# K22F.net
KiCad netlist of a schematic drawn in Altium Designer
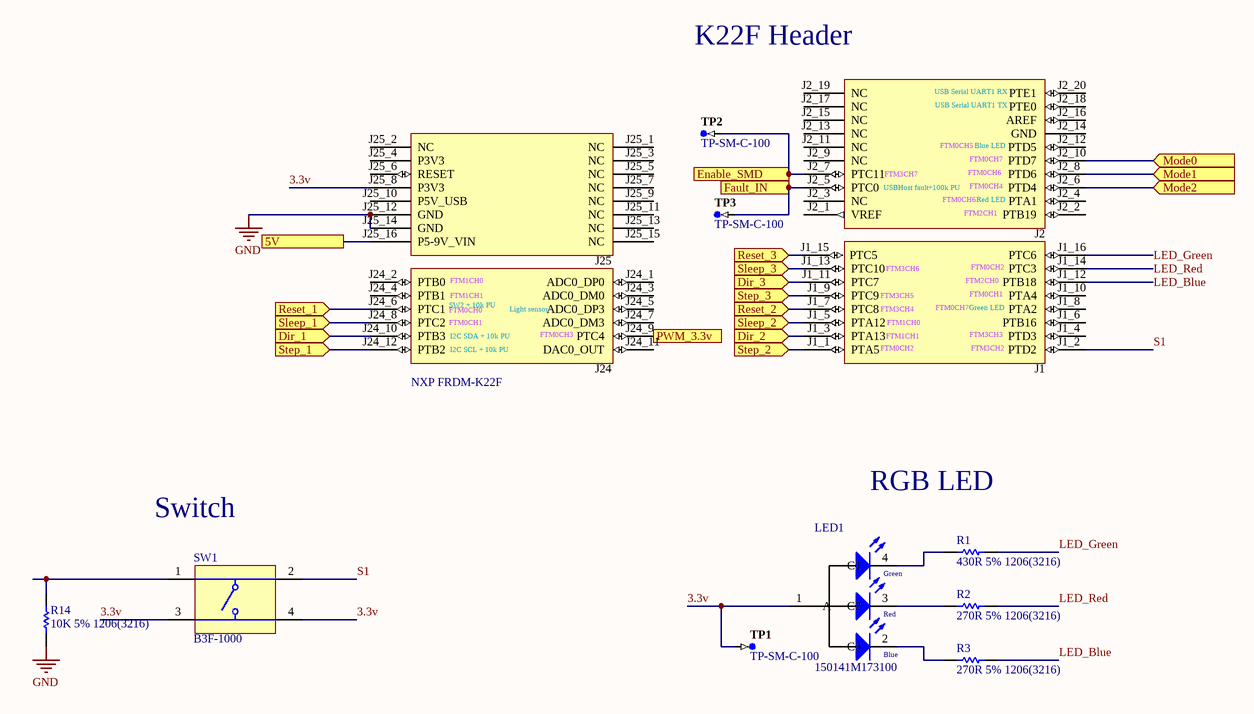
[diagram p0: K22F.SchDoc]

(export (version "E")
  (design (tool "Eeschema 10.0.6"))
  (components
    (comp (ref "*1")
      (value "NXP FRDM-K22F")
      (footprint "FRDM-K22F")
      (libsource (lib "JCULibrary_AS2 (1)") (part "NXP FRDM-K22F"))
    )
    (comp (ref "LED1")
      (value "150141M173100")
      (footprint "3528_A")
      (description "SMD Full-Color Top LED, WL-SFTW, Red & Green & Blue")
      (fields (field (name "MANUFACTURER") "Wuerth Elektronik"))
      (libsource (lib "Altium Content Vault") (part "WE-LED_RGB_A1B2R3G4-4"))
    )
    (comp (ref "R1")
      (value "430R 5% 1206(3216)")
      (footprint "RESC1206(3216)_L")
      (description "430R 0.25W 5% 1206 (3216 Metric)  SMD")
      (fields (field (name "POWER") "0.25 W") (field (name "TOLERANCE") "5 %"))
      (libsource (lib "Altium Content Vault") (part "RES"))
    )
    (comp (ref "R2")
      (value "270R 5% 1206(3216)")
      (footprint "RESC1206(3216)_N")
      (description "270R 0.25W 5% 1206 (3216 Metric)  SMD")
      (fields (field (name "TOLERANCE") "5 %") (field (name "POWER") "0.25 W"))
      (libsource (lib "Altium Content Vault") (part "RES"))
    )
    (comp (ref "R3")
      (value "270R 5% 1206(3216)")
      (footprint "RESC1206(3216)_N")
      (description "270R 0.25W 5% 1206 (3216 Metric)  SMD")
      (fields (field (name "TOLERANCE") "5 %") (field (name "POWER") "0.25 W"))
      (libsource (lib "Altium Content Vault") (part "RES"))
    )
    (comp (ref "R14")
      (value "10K 5% 1206(3216)")
      (footprint "RESC1206(3216)_M")
      (description "10K 0.25W 5% 1206 (3216 Metric)  SMD")
      (fields (field (name "POWER") "0.25 W") (field (name "TOLERANCE") "5 %"))
      (libsource (lib "Altium Content Vault") (part "RES"))
    )
    (comp (ref "SW1")
      (value "B3F-1000")
      (footprint "OMRON-B3F-1000-4_V")
      (description "Tactile Switch, SPST-NO, 0.05 A, 5 to 24 V, -25 to 70 degC, 4-Pin THD, RoHS, Bulk")
      (libsource (lib "Altium Content Vault") (part "SW-SPST-4_A"))
    )
    (comp (ref "TP1")
      (value "TP-SM-C-100")
      (footprint "TP-SM-C-100")
      (description "Test Point, Surface Mount, Circular, Pad Diameter 1 mm")
      (fields (field (name "MANUFACTURER") "No Vendor"))
      (libsource (lib "Altium Content Vault") (part "TP-SM"))
    )
    (comp (ref "TP2")
      (value "TP-SM-C-100")
      (footprint "TP-SM-C-100")
      (description "Test Point, Surface Mount, Circular, Pad Diameter 1 mm")
      (fields (field (name "MANUFACTURER") "No Vendor"))
      (libsource (lib "Altium Content Vault") (part "TP-SM"))
    )
    (comp (ref "TP3")
      (value "TP-SM-C-100")
      (footprint "TP-SM-C-100")
      (description "Test Point, Surface Mount, Circular, Pad Diameter 1 mm")
      (fields (field (name "MANUFACTURER") "No Vendor"))
      (libsource (lib "Altium Content Vault") (part "TP-SM"))
    )
  )
  (nets
    (net (code "1") (name "/3.3v") (class "Default")
      (node (ref "*1") (pin "J25_8") (pinfunction "P3V3_J25_8") (pintype "power_in"))
      (node (ref "LED1") (pin "1") (pinfunction "A_1") (pintype "passive"))
      (node (ref "SW1") (pin "3") (pinfunction "3_3") (pintype "passive"))
      (node (ref "SW1") (pin "4") (pinfunction "4_4") (pintype "passive"))
      (node (ref "TP1") (pin "1") (pinfunction "1_1") (pintype "input"))
    )
    (net (code "2") (name "/5V") (class "Default")
      (node (ref "*1") (pin "J25_16") (pinfunction "P5-9V_VIN_J25_16") (pintype "power_in"))
    )
    (net (code "3") (name "/Dir_1") (class "Default")
      (node (ref "*1") (pin "J24_10") (pinfunction "PTB3_J24_10") (pintype "bidirectional"))
    )
    (net (code "4") (name "/Dir_2") (class "Default")
      (node (ref "*1") (pin "J1_3") (pinfunction "PTA13_J1_3") (pintype "bidirectional"))
    )
    (net (code "5") (name "/Dir_3") (class "Default")
      (node (ref "*1") (pin "J1_11") (pinfunction "PTC7_J1_11") (pintype "bidirectional"))
    )
    (net (code "6") (name "/Enable_SMD") (class "Default")
      (node (ref "*1") (pin "J2_7") (pinfunction "PTC11_J2_7") (pintype "bidirectional"))
      (node (ref "TP2") (pin "1") (pinfunction "1_1") (pintype "input"))
    )
    (net (code "7") (name "/Fault_IN") (class "Default")
      (node (ref "*1") (pin "J2_5") (pinfunction "PTC0_J2_5") (pintype "bidirectional"))
      (node (ref "TP3") (pin "1") (pinfunction "1_1") (pintype "input"))
    )
    (net (code "8") (name "/LED_Blue") (class "Default")
      (node (ref "*1") (pin "J1_12") (pinfunction "PTB18_J1_12") (pintype "bidirectional"))
      (node (ref "R3") (pin "2") (pinfunction "2_2") (pintype "passive"))
    )
    (net (code "9") (name "/LED_Green") (class "Default")
      (node (ref "*1") (pin "J1_16") (pinfunction "PTC6_J1_16") (pintype "bidirectional"))
      (node (ref "R1") (pin "2") (pinfunction "2_2") (pintype "passive"))
    )
    (net (code "10") (name "/LED_Red") (class "Default")
      (node (ref "*1") (pin "J1_14") (pinfunction "PTC3_J1_14") (pintype "bidirectional"))
      (node (ref "R2") (pin "2") (pinfunction "2_2") (pintype "passive"))
    )
    (net (code "11") (name "/Mode0") (class "Default")
      (node (ref "*1") (pin "J2_10") (pinfunction "PTD7_J2_10") (pintype "bidirectional"))
    )
    (net (code "12") (name "/Mode1") (class "Default")
      (node (ref "*1") (pin "J2_8") (pinfunction "PTD6_J2_8") (pintype "bidirectional"))
    )
    (net (code "13") (name "/Mode2") (class "Default")
      (node (ref "*1") (pin "J2_6") (pinfunction "PTD4_J2_6") (pintype "bidirectional"))
    )
    (net (code "14") (name "/PWM_3.3v") (class "Default")
      (node (ref "*1") (pin "J24_9") (pinfunction "PTC4_J24_9") (pintype "bidirectional"))
    )
    (net (code "15") (name "/Reset_1") (class "Default")
      (node (ref "*1") (pin "J24_6") (pinfunction "PTC1_J24_6") (pintype "bidirectional"))
    )
    (net (code "16") (name "/Reset_2") (class "Default")
      (node (ref "*1") (pin "J1_7") (pinfunction "PTC8_J1_7") (pintype "bidirectional"))
    )
    (net (code "17") (name "/Reset_3") (class "Default")
      (node (ref "*1") (pin "J1_15") (pinfunction "PTC5_J1_15") (pintype "bidirectional"))
    )
    (net (code "18") (name "/S1") (class "Default")
      (node (ref "*1") (pin "J1_2") (pinfunction "PTD2_J1_2") (pintype "bidirectional"))
      (node (ref "SW1") (pin "2") (pinfunction "2_2") (pintype "passive"))
    )
    (net (code "19") (name "/Sleep_1") (class "Default")
      (node (ref "*1") (pin "J24_8") (pinfunction "PTC2_J24_8") (pintype "bidirectional"))
    )
    (net (code "20") (name "/Sleep_2") (class "Default")
      (node (ref "*1") (pin "J1_5") (pinfunction "PTA12_J1_5") (pintype "bidirectional"))
    )
    (net (code "21") (name "/Sleep_3") (class "Default")
      (node (ref "*1") (pin "J1_13") (pinfunction "PTC10_J1_13") (pintype "bidirectional"))
    )
    (net (code "22") (name "/Step_1") (class "Default")
      (node (ref "*1") (pin "J24_12") (pinfunction "PTB2_J24_12") (pintype "bidirectional"))
    )
    (net (code "23") (name "/Step_2") (class "Default")
      (node (ref "*1") (pin "J1_1") (pinfunction "PTA5_J1_1") (pintype "bidirectional"))
    )
    (net (code "24") (name "/Step_3") (class "Default")
      (node (ref "*1") (pin "J1_9") (pinfunction "PTC9_J1_9") (pintype "bidirectional"))
    )
    (net (code "25") (name "GND") (class "Default")
      (node (ref "*1") (pin "J25_12") (pinfunction "GND_J25_12") (pintype "power_in"))
      (node (ref "*1") (pin "J25_14") (pinfunction "GND_J25_14") (pintype "power_in"))
      (node (ref "R14") (pin "1") (pinfunction "1_1") (pintype "passive"))
    )
    (net (code "26") (name "Net-(LED1-C1)") (class "Default")
      (node (ref "LED1") (pin "4") (pinfunction "C1_4") (pintype "passive"))
      (node (ref "R1") (pin "1") (pinfunction "1_1") (pintype "passive"))
    )
    (net (code "27") (name "Net-(LED1-C2)") (class "Default")
      (node (ref "LED1") (pin "3") (pinfunction "C2_3") (pintype "passive"))
      (node (ref "R2") (pin "1") (pinfunction "1_1") (pintype "passive"))
    )
    (net (code "28") (name "Net-(LED1-C3)") (class "Default")
      (node (ref "LED1") (pin "2") (pinfunction "C3_2") (pintype "passive"))
      (node (ref "R3") (pin "1") (pinfunction "1_1") (pintype "passive"))
    )
    (net (code "29") (name "Net-(R14-Pad2)") (class "Default")
      (node (ref "R14") (pin "2") (pinfunction "2_2") (pintype "passive"))
      (node (ref "SW1") (pin "1") (pinfunction "1_1") (pintype "passive"))
    )
    (net (code "30") (name "unconnected-(*1-ADC0_DM0-PadJ24_3)") (class "Default")
      (node (ref "*1") (pin "J24_3") (pinfunction "ADC0_DM0_J24_3") (pintype "bidirectional"))
    )
    (net (code "31") (name "unconnected-(*1-ADC0_DM3-PadJ24_7)") (class "Default")
      (node (ref "*1") (pin "J24_7") (pinfunction "ADC0_DM3_J24_7") (pintype "bidirectional"))
    )
    (net (code "32") (name "unconnected-(*1-ADC0_DP0-PadJ24_1)") (class "Default")
      (node (ref "*1") (pin "J24_1") (pinfunction "ADC0_DP0_J24_1") (pintype "bidirectional"))
    )
    (net (code "33") (name "unconnected-(*1-ADC0_DP3-PadJ24_5)") (class "Default")
      (node (ref "*1") (pin "J24_5") (pinfunction "ADC0_DP3_J24_5") (pintype "bidirectional"))
    )
    (net (code "34") (name "unconnected-(*1-AREF-PadJ2_16)") (class "Default")
      (node (ref "*1") (pin "J2_16") (pinfunction "AREF_J2_16") (pintype "bidirectional"))
    )
    (net (code "35") (name "unconnected-(*1-DAC0_OUT-PadJ24_11)") (class "Default")
      (node (ref "*1") (pin "J24_11") (pinfunction "DAC0_OUT_J24_11") (pintype "bidirectional"))
    )
    (net (code "36") (name "unconnected-(*1-GND-PadJ2_14)") (class "Default")
      (node (ref "*1") (pin "J2_14") (pinfunction "GND_J2_14") (pintype "power_in"))
    )
    (net (code "37") (name "unconnected-(*1-NC-PadJ2_3)") (class "Default")
      (node (ref "*1") (pin "J2_3") (pinfunction "NC_J2_3") (pintype "passive"))
    )
    (net (code "38") (name "unconnected-(*1-NC-PadJ2_9)") (class "Default")
      (node (ref "*1") (pin "J2_9") (pinfunction "NC_J2_9") (pintype "passive"))
    )
    (net (code "39") (name "unconnected-(*1-NC-PadJ2_11)") (class "Default")
      (node (ref "*1") (pin "J2_11") (pinfunction "NC_J2_11") (pintype "passive"))
    )
    (net (code "40") (name "unconnected-(*1-NC-PadJ2_13)") (class "Default")
      (node (ref "*1") (pin "J2_13") (pinfunction "NC_J2_13") (pintype "passive"))
    )
    (net (code "41") (name "unconnected-(*1-NC-PadJ2_15)") (class "Default")
      (node (ref "*1") (pin "J2_15") (pinfunction "NC_J2_15") (pintype "passive"))
    )
    (net (code "42") (name "unconnected-(*1-NC-PadJ2_17)") (class "Default")
      (node (ref "*1") (pin "J2_17") (pinfunction "NC_J2_17") (pintype "passive"))
    )
    (net (code "43") (name "unconnected-(*1-NC-PadJ2_19)") (class "Default")
      (node (ref "*1") (pin "J2_19") (pinfunction "NC_J2_19") (pintype "passive"))
    )
    (net (code "44") (name "unconnected-(*1-NC-PadJ25_1)") (class "Default")
      (node (ref "*1") (pin "J25_1") (pinfunction "NC_J25_1") (pintype "passive"))
    )
    (net (code "45") (name "unconnected-(*1-NC-PadJ25_2)") (class "Default")
      (node (ref "*1") (pin "J25_2") (pinfunction "NC_J25_2") (pintype "passive"))
    )
    (net (code "46") (name "unconnected-(*1-NC-PadJ25_3)") (class "Default")
      (node (ref "*1") (pin "J25_3") (pinfunction "NC_J25_3") (pintype "passive"))
    )
    (net (code "47") (name "unconnected-(*1-NC-PadJ25_5)") (class "Default")
      (node (ref "*1") (pin "J25_5") (pinfunction "NC_J25_5") (pintype "passive"))
    )
    (net (code "48") (name "unconnected-(*1-NC-PadJ25_7)") (class "Default")
      (node (ref "*1") (pin "J25_7") (pinfunction "NC_J25_7") (pintype "passive"))
    )
    (net (code "49") (name "unconnected-(*1-NC-PadJ25_9)") (class "Default")
      (node (ref "*1") (pin "J25_9") (pinfunction "NC_J25_9") (pintype "passive"))
    )
    (net (code "50") (name "unconnected-(*1-NC-PadJ25_11)") (class "Default")
      (node (ref "*1") (pin "J25_11") (pinfunction "NC_J25_11") (pintype "passive"))
    )
    (net (code "51") (name "unconnected-(*1-NC-PadJ25_13)") (class "Default")
      (node (ref "*1") (pin "J25_13") (pinfunction "NC_J25_13") (pintype "passive"))
    )
    (net (code "52") (name "unconnected-(*1-NC-PadJ25_15)") (class "Default")
      (node (ref "*1") (pin "J25_15") (pinfunction "NC_J25_15") (pintype "passive"))
    )
    (net (code "53") (name "unconnected-(*1-P3V3-PadJ25_4)") (class "Default")
      (node (ref "*1") (pin "J25_4") (pinfunction "P3V3_J25_4") (pintype "power_in"))
    )
    (net (code "54") (name "unconnected-(*1-P5V_USB-PadJ25_10)") (class "Default")
      (node (ref "*1") (pin "J25_10") (pinfunction "P5V_USB_J25_10") (pintype "power_in"))
    )
    (net (code "55") (name "unconnected-(*1-PTA1-PadJ2_4)") (class "Default")
      (node (ref "*1") (pin "J2_4") (pinfunction "PTA1_J2_4") (pintype "bidirectional"))
    )
    (net (code "56") (name "unconnected-(*1-PTA2-PadJ1_8)") (class "Default")
      (node (ref "*1") (pin "J1_8") (pinfunction "PTA2_J1_8") (pintype "bidirectional"))
    )
    (net (code "57") (name "unconnected-(*1-PTA4-PadJ1_10)") (class "Default")
      (node (ref "*1") (pin "J1_10") (pinfunction "PTA4_J1_10") (pintype "bidirectional"))
    )
    (net (code "58") (name "unconnected-(*1-PTB0-PadJ24_2)") (class "Default")
      (node (ref "*1") (pin "J24_2") (pinfunction "PTB0_J24_2") (pintype "bidirectional"))
    )
    (net (code "59") (name "unconnected-(*1-PTB1-PadJ24_4)") (class "Default")
      (node (ref "*1") (pin "J24_4") (pinfunction "PTB1_J24_4") (pintype "bidirectional"))
    )
    (net (code "60") (name "unconnected-(*1-PTB16-PadJ1_6)") (class "Default")
      (node (ref "*1") (pin "J1_6") (pinfunction "PTB16_J1_6") (pintype "bidirectional"))
    )
    (net (code "61") (name "unconnected-(*1-PTB19-PadJ2_2)") (class "Default")
      (node (ref "*1") (pin "J2_2") (pinfunction "PTB19_J2_2") (pintype "bidirectional"))
    )
    (net (code "62") (name "unconnected-(*1-PTD3-PadJ1_4)") (class "Default")
      (node (ref "*1") (pin "J1_4") (pinfunction "PTD3_J1_4") (pintype "bidirectional"))
    )
    (net (code "63") (name "unconnected-(*1-PTD5-PadJ2_12)") (class "Default")
      (node (ref "*1") (pin "J2_12") (pinfunction "PTD5_J2_12") (pintype "bidirectional"))
    )
    (net (code "64") (name "unconnected-(*1-PTE0-PadJ2_18)") (class "Default")
      (node (ref "*1") (pin "J2_18") (pinfunction "PTE0_J2_18") (pintype "bidirectional"))
    )
    (net (code "65") (name "unconnected-(*1-PTE1-PadJ2_20)") (class "Default")
      (node (ref "*1") (pin "J2_20") (pinfunction "PTE1_J2_20") (pintype "bidirectional"))
    )
    (net (code "66") (name "unconnected-(*1-RESET-PadJ25_6)") (class "Default")
      (node (ref "*1") (pin "J25_6") (pinfunction "RESET_J25_6") (pintype "bidirectional"))
    )
    (net (code "67") (name "unconnected-(*1-VREF-PadJ2_1)") (class "Default")
      (node (ref "*1") (pin "J2_1") (pinfunction "VREF_J2_1") (pintype "output"))
    )
  )
)
